# 1-voice_1_1.net
KiCad netlist of a schematic drawn in EAGLE
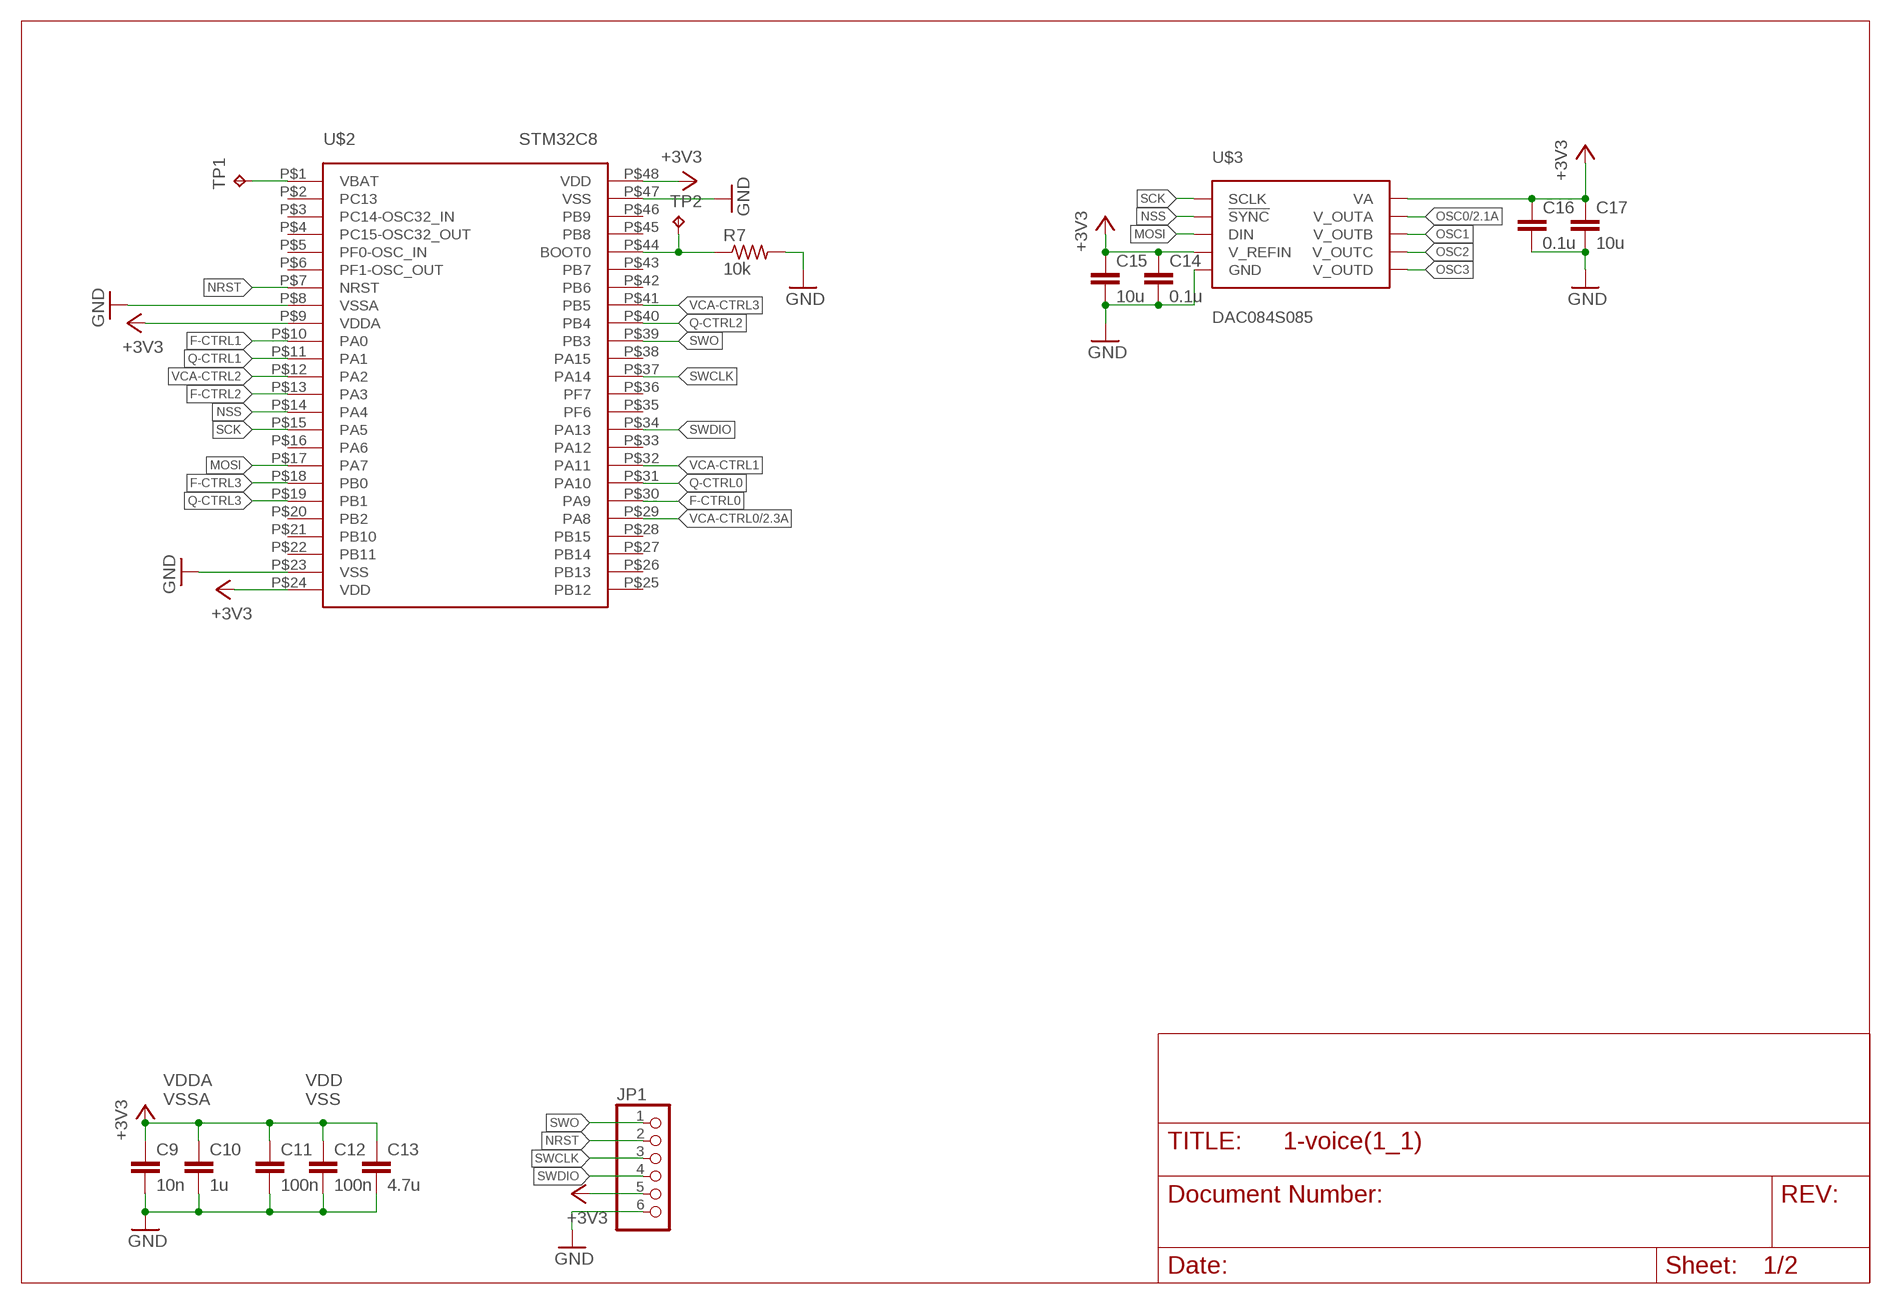
[diagram p0: schematic, sheet 1]
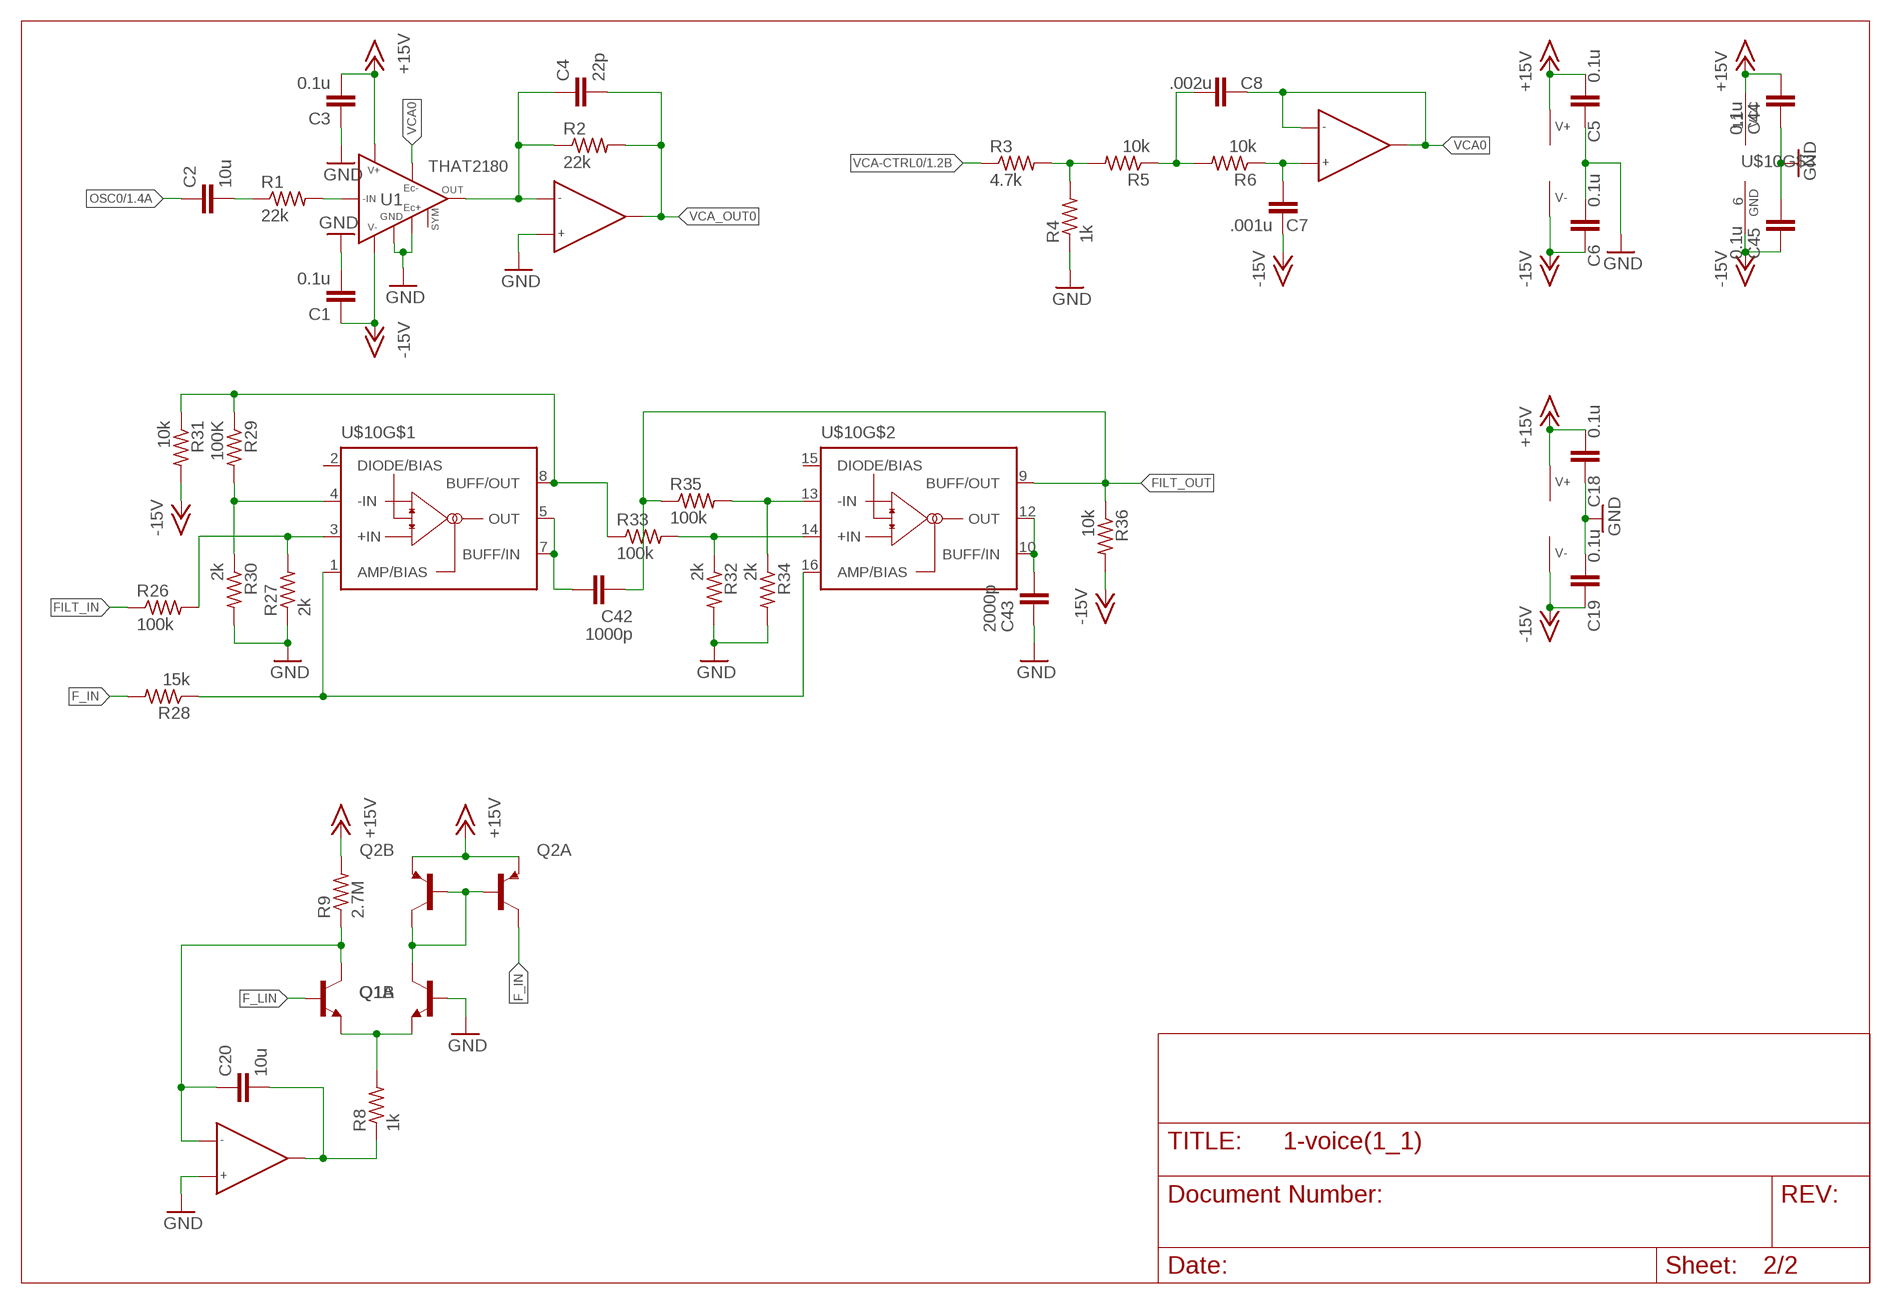
[diagram p1: schematic, sheet 2]

(export (version "E")
  (design (tool "Eeschema 10.0.6"))
  (components
    (comp (ref "C1")
      (value "0.1u")
      (footprint "eagle-import:C1206")
      (libsource (lib "eagle-import") (part "C-EUC1206"))
    )
    (comp (ref "C2")
      (value "10u")
      (footprint "eagle-import:C1206")
      (libsource (lib "eagle-import") (part "C-EUC1206"))
    )
    (comp (ref "C3")
      (value "0.1u")
      (footprint "eagle-import:C1206")
      (libsource (lib "eagle-import") (part "C-EUC1206"))
    )
    (comp (ref "C4")
      (value "22p")
      (footprint "eagle-import:C1206")
      (libsource (lib "eagle-import") (part "C-EUC1206"))
    )
    (comp (ref "C5")
      (value "0.1u")
      (footprint "eagle-import:C1206")
      (libsource (lib "eagle-import") (part "C-EUC1206"))
    )
    (comp (ref "C6")
      (value "0.1u")
      (footprint "eagle-import:C1206")
      (libsource (lib "eagle-import") (part "C-EUC1206"))
    )
    (comp (ref "C7")
      (value ".001u")
      (footprint "eagle-import:C1206")
      (libsource (lib "eagle-import") (part "C-EUC1206"))
    )
    (comp (ref "C8")
      (value ".002u")
      (footprint "eagle-import:C1206")
      (libsource (lib "eagle-import") (part "C-EUC1206"))
    )
    (comp (ref "C18")
      (value "0.1u")
      (footprint "eagle-import:C1206")
      (libsource (lib "eagle-import") (part "C-EUC1206"))
    )
    (comp (ref "C19")
      (value "0.1u")
      (footprint "eagle-import:C1206")
      (libsource (lib "eagle-import") (part "C-EUC1206"))
    )
    (comp (ref "C20")
      (value "10u")
      (footprint "eagle-import:C1206")
      (libsource (lib "eagle-import") (part "C-EUC1206"))
    )
    (comp (ref "C42")
      (value "1000p")
      (footprint "eagle-import:C1206")
      (libsource (lib "eagle-import") (part "resistor_348_C-EUC1206"))
    )
    (comp (ref "C43")
      (value "2000p")
      (footprint "eagle-import:C1206")
      (libsource (lib "eagle-import") (part "resistor_348_C-EUC1206"))
    )
    (comp (ref "C44")
      (value "0.1u")
      (footprint "eagle-import:C1206")
      (libsource (lib "eagle-import") (part "resistor_348_C-EUC1206"))
    )
    (comp (ref "C45")
      (value "0.1u")
      (footprint "eagle-import:C1206")
      (libsource (lib "eagle-import") (part "resistor_348_C-EUC1206"))
    )
    (comp (ref "Q1")
      (value "TRANS-BJT_NPN-DUAL-BC847BS-JBLMASK")
      (footprint "eagle-import:SOT-363-JBLMASK")
      (libsource (lib "eagle-import") (part "TRANS-BJT_NPN-DUAL-BC847BS-JBLMASK"))
    )
    (comp (ref "Q2")
      (value "TRANS-BJT_PNP-DUAL-BC857-JBLMASK")
      (footprint "eagle-import:SOT-363-JBLMASK")
      (libsource (lib "eagle-import") (part "TRANS-BJT_PNP-DUAL-BC857-JBLMASK"))
    )
    (comp (ref "R1")
      (value "22k")
      (footprint "eagle-import:R1206")
      (libsource (lib "eagle-import") (part "R-US_R1206"))
    )
    (comp (ref "R2")
      (value "22k")
      (footprint "eagle-import:R1206")
      (libsource (lib "eagle-import") (part "R-US_R1206"))
    )
    (comp (ref "R3")
      (value "4.7k")
      (footprint "eagle-import:R1206")
      (libsource (lib "eagle-import") (part "R-US_R1206"))
    )
    (comp (ref "R4")
      (value "1k")
      (footprint "eagle-import:R1206")
      (libsource (lib "eagle-import") (part "R-US_R1206"))
    )
    (comp (ref "R5")
      (value "10k")
      (footprint "eagle-import:R1206")
      (libsource (lib "eagle-import") (part "R-US_R1206"))
    )
    (comp (ref "R6")
      (value "10k")
      (footprint "eagle-import:R1206")
      (libsource (lib "eagle-import") (part "R-US_R1206"))
    )
    (comp (ref "R8")
      (value "1k")
      (footprint "eagle-import:R1206")
      (libsource (lib "eagle-import") (part "resistor_348_R-US_R1206"))
    )
    (comp (ref "R9")
      (value "2.7M")
      (footprint "eagle-import:R1206")
      (libsource (lib "eagle-import") (part "resistor_348_R-US_R1206"))
    )
    (comp (ref "R26")
      (value "100k")
      (footprint "eagle-import:R1206")
      (libsource (lib "eagle-import") (part "resistor_348_R-US_R1206"))
    )
    (comp (ref "R27")
      (value "2k")
      (footprint "eagle-import:R1206")
      (libsource (lib "eagle-import") (part "resistor_348_R-US_R1206"))
    )
    (comp (ref "R28")
      (value "15k")
      (footprint "eagle-import:R1206")
      (libsource (lib "eagle-import") (part "resistor_348_R-US_R1206"))
    )
    (comp (ref "R29")
      (value "100K")
      (footprint "eagle-import:R1206")
      (libsource (lib "eagle-import") (part "resistor_348_R-US_R1206"))
    )
    (comp (ref "R30")
      (value "2k")
      (footprint "eagle-import:R1206")
      (libsource (lib "eagle-import") (part "resistor_348_R-US_R1206"))
    )
    (comp (ref "R31")
      (value "10k")
      (footprint "eagle-import:R1206")
      (libsource (lib "eagle-import") (part "resistor_348_R-US_R1206"))
    )
    (comp (ref "R32")
      (value "2k")
      (footprint "eagle-import:R1206")
      (libsource (lib "eagle-import") (part "resistor_348_R-US_R1206"))
    )
    (comp (ref "R33")
      (value "100k")
      (footprint "eagle-import:R1206")
      (libsource (lib "eagle-import") (part "resistor_348_R-US_R1206"))
    )
    (comp (ref "R34")
      (value "2k")
      (footprint "eagle-import:R1206")
      (libsource (lib "eagle-import") (part "resistor_348_R-US_R1206"))
    )
    (comp (ref "R35")
      (value "100k")
      (footprint "eagle-import:R1206")
      (libsource (lib "eagle-import") (part "resistor_348_R-US_R1206"))
    )
    (comp (ref "R36")
      (value "10k")
      (footprint "eagle-import:R1206")
      (libsource (lib "eagle-import") (part "resistor_348_R-US_R1206"))
    )
    (comp (ref "U$1")
      (value "TL072")
      (footprint "eagle-import:SOIC8")
      (libsource (lib "eagle-import") (part "TL072"))
    )
    (comp (ref "U$10")
      (value "XX-13700DMP16")
      (footprint "eagle-import:DMP16")
      (libsource (lib "eagle-import") (part "XX-13700DMP16"))
    )
    (comp (ref "U$11")
      (value "TL072")
      (footprint "eagle-import:SOIC8")
      (libsource (lib "eagle-import") (part "TL072"))
    )
    (comp (ref "U1")
      (value "THAT2180")
      (footprint "eagle-import:SIP8")
      (libsource (lib "eagle-import") (part "THAT2180"))
    )
    (comp (ref "C9")
      (value "10n")
      (footprint "eagle-import:C1206")
      (libsource (lib "eagle-import") (part "C-EUC1206"))
    )
    (comp (ref "C10")
      (value "1u")
      (footprint "eagle-import:C1206")
      (libsource (lib "eagle-import") (part "C-EUC1206"))
    )
    (comp (ref "C11")
      (value "100n")
      (footprint "eagle-import:C1206")
      (libsource (lib "eagle-import") (part "C-EUC1206"))
    )
    (comp (ref "C12")
      (value "100n")
      (footprint "eagle-import:C1206")
      (libsource (lib "eagle-import") (part "C-EUC1206"))
    )
    (comp (ref "C13")
      (value "4.7u")
      (footprint "eagle-import:C1206")
      (libsource (lib "eagle-import") (part "C-EUC1206"))
    )
    (comp (ref "C14")
      (value "0.1u")
      (footprint "eagle-import:C1206")
      (libsource (lib "eagle-import") (part "C-EUC1206"))
    )
    (comp (ref "C15")
      (value "10u")
      (footprint "eagle-import:C1206")
      (libsource (lib "eagle-import") (part "C-EUC1206"))
    )
    (comp (ref "C16")
      (value "0.1u")
      (footprint "eagle-import:C1206")
      (libsource (lib "eagle-import") (part "C-EUC1206"))
    )
    (comp (ref "C17")
      (value "10u")
      (footprint "eagle-import:C1206")
      (libsource (lib "eagle-import") (part "C-EUC1206"))
    )
    (comp (ref "JP1")
      (value "PINHD-1X6")
      (footprint "eagle-import:1X06")
      (libsource (lib "eagle-import") (part "PINHD-1X6"))
    )
    (comp (ref "R7")
      (value "10k")
      (footprint "eagle-import:R1206")
      (libsource (lib "eagle-import") (part "R-US_R1206"))
    )
    (comp (ref "TP1")
      (value "TPPAD1-13")
      (footprint "eagle-import:P1-13")
      (libsource (lib "eagle-import") (part "TPPAD1-13"))
    )
    (comp (ref "TP2")
      (value "TPPAD1-13")
      (footprint "eagle-import:P1-13")
      (libsource (lib "eagle-import") (part "TPPAD1-13"))
    )
    (comp (ref "U$2")
      (value "STM32C8")
      (footprint "eagle-import:LQFP48")
      (libsource (lib "eagle-import") (part "STM32C8"))
    )
    (comp (ref "U$3")
      (value "DAC084S085")
      (footprint "eagle-import:VSSOP10")
      (libsource (lib "eagle-import") (part "DAC084S085"))
    )
  )
  (nets
    (net (code "1") (name "+3V3") (class "Default")
      (node (ref "C10") (pin "1") (pinfunction "1_1") (pintype "passive"))
      (node (ref "C11") (pin "1") (pinfunction "1_1") (pintype "passive"))
      (node (ref "C12") (pin "1") (pinfunction "1_1") (pintype "passive"))
      (node (ref "C13") (pin "1") (pinfunction "1_1") (pintype "passive"))
      (node (ref "C14") (pin "1") (pinfunction "1_1") (pintype "passive"))
      (node (ref "C15") (pin "1") (pinfunction "1_1") (pintype "passive"))
      (node (ref "C16") (pin "1") (pinfunction "1_1") (pintype "passive"))
      (node (ref "C17") (pin "1") (pinfunction "1_1") (pintype "passive"))
      (node (ref "C9") (pin "1") (pinfunction "1_1") (pintype "passive"))
      (node (ref "JP1") (pin "5") (pinfunction "5_5") (pintype "passive"))
      (node (ref "U$2") (pin "P$24") (pinfunction "VDD_P$24") (pintype "bidirectional"))
      (node (ref "U$2") (pin "P$48") (pinfunction "VDD_P$48") (pintype "bidirectional"))
      (node (ref "U$2") (pin "P$9") (pinfunction "VDDA_P$9") (pintype "bidirectional"))
      (node (ref "U$3") (pin "P$1") (pinfunction "VA_P$1") (pintype "bidirectional"))
      (node (ref "U$3") (pin "P$7") (pinfunction "V_REFIN_P$7") (pintype "bidirectional"))
    )
    (net (code "2") (name "+15V") (class "Default")
      (node (ref "C18") (pin "2") (pinfunction "2_2") (pintype "passive"))
      (node (ref "C3") (pin "2") (pinfunction "2_2") (pintype "passive"))
      (node (ref "C44") (pin "1") (pinfunction "1_1") (pintype "passive"))
      (node (ref "C5") (pin "2") (pinfunction "2_2") (pintype "passive"))
      (node (ref "Q2") (pin "1") (pinfunction "E_1") (pintype "passive"))
      (node (ref "Q2") (pin "4") (pinfunction "E_4") (pintype "passive"))
      (node (ref "R9") (pin "2") (pinfunction "2_2") (pintype "passive"))
      (node (ref "U$1") (pin "P$8") (pinfunction "V+_P$8") (pintype "bidirectional"))
      (node (ref "U$10") (pin "11") (pinfunction "VCC_11") (pintype "power_in"))
      (node (ref "U$11") (pin "P$8") (pinfunction "V+_P$8") (pintype "bidirectional"))
      (node (ref "U1") (pin "$P7") (pinfunction "V+_$P7") (pintype "bidirectional"))
    )
    (net (code "3") (name "-15V") (class "Default")
      (node (ref "C1") (pin "1") (pinfunction "1_1") (pintype "passive"))
      (node (ref "C19") (pin "1") (pinfunction "1_1") (pintype "passive"))
      (node (ref "C45") (pin "2") (pinfunction "2_2") (pintype "passive"))
      (node (ref "C6") (pin "1") (pinfunction "1_1") (pintype "passive"))
      (node (ref "C7") (pin "1") (pinfunction "1_1") (pintype "passive"))
      (node (ref "R31") (pin "2") (pinfunction "2_2") (pintype "passive"))
      (node (ref "R36") (pin "2") (pinfunction "2_2") (pintype "passive"))
      (node (ref "U$1") (pin "P$4") (pinfunction "V-_P$4") (pintype "bidirectional"))
      (node (ref "U$10") (pin "6") (pinfunction "GND_6") (pintype "power_in"))
      (node (ref "U$11") (pin "P$4") (pinfunction "V-_P$4") (pintype "bidirectional"))
      (node (ref "U1") (pin "$P5") (pinfunction "V-_$P5") (pintype "bidirectional"))
    )
    (net (code "4") (name "F-CTRL0") (class "Default")
      (node (ref "U$2") (pin "P$30") (pinfunction "PA9_P$30") (pintype "bidirectional"))
    )
    (net (code "5") (name "F-CTRL1") (class "Default")
      (node (ref "U$2") (pin "P$10") (pinfunction "PA0_P$10") (pintype "bidirectional"))
    )
    (net (code "6") (name "F-CTRL2") (class "Default")
      (node (ref "U$2") (pin "P$13") (pinfunction "PA3_P$13") (pintype "bidirectional"))
    )
    (net (code "7") (name "F-CTRL3") (class "Default")
      (node (ref "U$2") (pin "P$18") (pinfunction "PB0_P$18") (pintype "bidirectional"))
    )
    (net (code "8") (name "FILT_IN") (class "Default")
      (node (ref "R26") (pin "1") (pinfunction "1_1") (pintype "passive"))
    )
    (net (code "9") (name "FILT_OUT") (class "Default")
      (node (ref "C42") (pin "2") (pinfunction "2_2") (pintype "passive"))
      (node (ref "R35") (pin "1") (pinfunction "1_1") (pintype "passive"))
      (node (ref "R36") (pin "1") (pinfunction "1_1") (pintype "passive"))
      (node (ref "U$10") (pin "9") (pinfunction "BUFF/OUT_9") (pintype "output"))
    )
    (net (code "10") (name "F_IN") (class "Default")
      (node (ref "Q2") (pin "6") (pinfunction "C_6") (pintype "passive"))
      (node (ref "R28") (pin "2") (pinfunction "2_2") (pintype "passive"))
    )
    (net (code "11") (name "F_LIN") (class "Default")
      (node (ref "Q1") (pin "2") (pinfunction "B_2") (pintype "passive"))
    )
    (net (code "12") (name "GND") (class "Default")
      (node (ref "C1") (pin "2") (pinfunction "2_2") (pintype "passive"))
      (node (ref "C10") (pin "2") (pinfunction "2_2") (pintype "passive"))
      (node (ref "C11") (pin "2") (pinfunction "2_2") (pintype "passive"))
      (node (ref "C12") (pin "2") (pinfunction "2_2") (pintype "passive"))
      (node (ref "C13") (pin "2") (pinfunction "2_2") (pintype "passive"))
      (node (ref "C14") (pin "2") (pinfunction "2_2") (pintype "passive"))
      (node (ref "C15") (pin "2") (pinfunction "2_2") (pintype "passive"))
      (node (ref "C16") (pin "2") (pinfunction "2_2") (pintype "passive"))
      (node (ref "C17") (pin "2") (pinfunction "2_2") (pintype "passive"))
      (node (ref "C18") (pin "1") (pinfunction "1_1") (pintype "passive"))
      (node (ref "C19") (pin "2") (pinfunction "2_2") (pintype "passive"))
      (node (ref "C3") (pin "1") (pinfunction "1_1") (pintype "passive"))
      (node (ref "C43") (pin "2") (pinfunction "2_2") (pintype "passive"))
      (node (ref "C44") (pin "2") (pinfunction "2_2") (pintype "passive"))
      (node (ref "C45") (pin "1") (pinfunction "1_1") (pintype "passive"))
      (node (ref "C5") (pin "1") (pinfunction "1_1") (pintype "passive"))
      (node (ref "C6") (pin "2") (pinfunction "2_2") (pintype "passive"))
      (node (ref "C9") (pin "2") (pinfunction "2_2") (pintype "passive"))
      (node (ref "JP1") (pin "6") (pinfunction "6_6") (pintype "passive"))
      (node (ref "Q1") (pin "5") (pinfunction "B_5") (pintype "passive"))
      (node (ref "R27") (pin "1") (pinfunction "1_1") (pintype "passive"))
      (node (ref "R30") (pin "2") (pinfunction "2_2") (pintype "passive"))
      (node (ref "R32") (pin "2") (pinfunction "2_2") (pintype "passive"))
      (node (ref "R34") (pin "2") (pinfunction "2_2") (pintype "passive"))
      (node (ref "R4") (pin "1") (pinfunction "1_1") (pintype "passive"))
      (node (ref "R7") (pin "2") (pinfunction "2_2") (pintype "passive"))
      (node (ref "U$1") (pin "P$3") (pinfunction "IN+_P$3") (pintype "bidirectional"))
      (node (ref "U$11") (pin "P$3") (pinfunction "IN+_P$3") (pintype "bidirectional"))
      (node (ref "U$2") (pin "P$23") (pinfunction "VSS_P$23") (pintype "bidirectional"))
      (node (ref "U$2") (pin "P$47") (pinfunction "VSS_P$47") (pintype "bidirectional"))
      (node (ref "U$2") (pin "P$8") (pinfunction "VSSA_P$8") (pintype "bidirectional"))
      (node (ref "U$3") (pin "P$6") (pinfunction "GND_P$6") (pintype "bidirectional"))
      (node (ref "U1") (pin "$P2") (pinfunction "EC+_$P2") (pintype "bidirectional"))
      (node (ref "U1") (pin "$P6") (pinfunction "GND_$P6") (pintype "bidirectional"))
    )
    (net (code "13") (name "MOSI") (class "Default")
      (node (ref "U$2") (pin "P$17") (pinfunction "PA7_P$17") (pintype "bidirectional"))
      (node (ref "U$3") (pin "P$8") (pinfunction "DIN_P$8") (pintype "bidirectional"))
    )
    (net (code "14") (name "NRST") (class "Default")
      (node (ref "JP1") (pin "2") (pinfunction "2_2") (pintype "passive"))
      (node (ref "U$2") (pin "P$7") (pinfunction "NRST_P$7") (pintype "bidirectional"))
    )
    (net (code "15") (name "NSS") (class "Default")
      (node (ref "U$2") (pin "P$14") (pinfunction "PA4_P$14") (pintype "bidirectional"))
      (node (ref "U$3") (pin "P$9") (pinfunction "~{SYNC}_P$9") (pintype "bidirectional"))
    )
    (net (code "16") (name "Net-(C2-Pad2)") (class "Default")
      (node (ref "C2") (pin "2") (pinfunction "2_2") (pintype "passive"))
      (node (ref "R1") (pin "1") (pinfunction "1_1") (pintype "passive"))
    )
    (net (code "17") (name "Net-(C8-Pad2)") (class "Default")
      (node (ref "C8") (pin "2") (pinfunction "2_2") (pintype "passive"))
      (node (ref "R5") (pin "1") (pinfunction "1_1") (pintype "passive"))
      (node (ref "R6") (pin "2") (pinfunction "2_2") (pintype "passive"))
    )
    (net (code "18") (name "Net-(Q1A-C)") (class "Default")
      (node (ref "C20") (pin "1") (pinfunction "1_1") (pintype "passive"))
      (node (ref "Q1") (pin "6") (pinfunction "C_6") (pintype "passive"))
      (node (ref "R9") (pin "1") (pinfunction "1_1") (pintype "passive"))
      (node (ref "U$11") (pin "P$2") (pinfunction "IN-_P$2") (pintype "bidirectional"))
    )
    (net (code "19") (name "Net-(Q1A-E)") (class "Default")
      (node (ref "Q1") (pin "1") (pinfunction "E_1") (pintype "passive"))
      (node (ref "Q1") (pin "4") (pinfunction "E_4") (pintype "passive"))
      (node (ref "R8") (pin "2") (pinfunction "2_2") (pintype "passive"))
    )
    (net (code "20") (name "Net-(Q1B-C)") (class "Default")
      (node (ref "Q1") (pin "3") (pinfunction "C_3") (pintype "passive"))
      (node (ref "Q2") (pin "2") (pinfunction "B_2") (pintype "passive"))
      (node (ref "Q2") (pin "3") (pinfunction "C_3") (pintype "passive"))
      (node (ref "Q2") (pin "5") (pinfunction "B_5") (pintype "passive"))
    )
    (net (code "21") (name "Net-(R3-Pad2)") (class "Default")
      (node (ref "R3") (pin "2") (pinfunction "2_2") (pintype "passive"))
      (node (ref "R4") (pin "2") (pinfunction "2_2") (pintype "passive"))
      (node (ref "R5") (pin "2") (pinfunction "2_2") (pintype "passive"))
    )
    (net (code "22") (name "Net-(U$1A-IN-)") (class "Default")
      (node (ref "C4") (pin "1") (pinfunction "1_1") (pintype "passive"))
      (node (ref "R2") (pin "1") (pinfunction "1_1") (pintype "passive"))
      (node (ref "U$1") (pin "P$2") (pinfunction "IN-_P$2") (pintype "bidirectional"))
      (node (ref "U1") (pin "$P8") (pinfunction "OUT_$P8") (pintype "bidirectional"))
    )
    (net (code "23") (name "Net-(U$1B-IN+)") (class "Default")
      (node (ref "C7") (pin "2") (pinfunction "2_2") (pintype "passive"))
      (node (ref "R6") (pin "1") (pinfunction "1_1") (pintype "passive"))
      (node (ref "U$1") (pin "P$5") (pinfunction "IN+_P$5") (pintype "bidirectional"))
    )
    (net (code "24") (name "Net-(U$2-BOOT0)") (class "Default")
      (node (ref "R7") (pin "1") (pinfunction "1_1") (pintype "passive"))
      (node (ref "TP2") (pin "TP") (pinfunction "TP_TP") (pintype "input"))
      (node (ref "U$2") (pin "P$44") (pinfunction "BOOT0_P$44") (pintype "bidirectional"))
    )
    (net (code "25") (name "Net-(U$2-VBAT)") (class "Default")
      (node (ref "TP1") (pin "TP") (pinfunction "TP_TP") (pintype "input"))
      (node (ref "U$2") (pin "P$1") (pinfunction "VBAT_P$1") (pintype "bidirectional"))
    )
    (net (code "26") (name "Net-(U$10A-+IN)") (class "Default")
      (node (ref "R26") (pin "2") (pinfunction "2_2") (pintype "passive"))
      (node (ref "R27") (pin "2") (pinfunction "2_2") (pintype "passive"))
      (node (ref "U$10") (pin "3") (pinfunction "+IN_3") (pintype "input"))
    )
    (net (code "27") (name "Net-(U$10A--IN)") (class "Default")
      (node (ref "R29") (pin "2") (pinfunction "2_2") (pintype "passive"))
      (node (ref "R30") (pin "1") (pinfunction "1_1") (pintype "passive"))
      (node (ref "U$10") (pin "4") (pinfunction "-IN_4") (pintype "input"))
    )
    (net (code "28") (name "Net-(U$10A-AMP{slash}BIAS)") (class "Default")
      (node (ref "R28") (pin "1") (pinfunction "1_1") (pintype "passive"))
      (node (ref "U$10") (pin "1") (pinfunction "AMP/BIAS_1") (pintype "passive"))
      (node (ref "U$10") (pin "16") (pinfunction "AMP/BIAS_16") (pintype "passive"))
    )
    (net (code "29") (name "Net-(U$10A-BUFF{slash}IN)") (class "Default")
      (node (ref "C42") (pin "1") (pinfunction "1_1") (pintype "passive"))
      (node (ref "U$10") (pin "5") (pinfunction "OUT_5") (pintype "output"))
      (node (ref "U$10") (pin "7") (pinfunction "BUFF/IN_7") (pintype "input"))
    )
    (net (code "30") (name "Net-(U$10A-BUFF{slash}OUT)") (class "Default")
      (node (ref "R29") (pin "1") (pinfunction "1_1") (pintype "passive"))
      (node (ref "R31") (pin "1") (pinfunction "1_1") (pintype "passive"))
      (node (ref "R33") (pin "1") (pinfunction "1_1") (pintype "passive"))
      (node (ref "U$10") (pin "8") (pinfunction "BUFF/OUT_8") (pintype "output"))
    )
    (net (code "31") (name "Net-(U$10B-+IN)") (class "Default")
      (node (ref "R32") (pin "1") (pinfunction "1_1") (pintype "passive"))
      (node (ref "R33") (pin "2") (pinfunction "2_2") (pintype "passive"))
      (node (ref "U$10") (pin "14") (pinfunction "+IN_14") (pintype "input"))
    )
    (net (code "32") (name "Net-(U$10B--IN)") (class "Default")
      (node (ref "R34") (pin "1") (pinfunction "1_1") (pintype "passive"))
      (node (ref "R35") (pin "2") (pinfunction "2_2") (pintype "passive"))
      (node (ref "U$10") (pin "13") (pinfunction "-IN_13") (pintype "input"))
    )
    (net (code "33") (name "Net-(U$10B-BUFF{slash}IN)") (class "Default")
      (node (ref "C43") (pin "1") (pinfunction "1_1") (pintype "passive"))
      (node (ref "U$10") (pin "10") (pinfunction "BUFF/IN_10") (pintype "input"))
      (node (ref "U$10") (pin "12") (pinfunction "OUT_12") (pintype "output"))
    )
    (net (code "34") (name "Net-(U$11A-OUT)") (class "Default")
      (node (ref "C20") (pin "2") (pinfunction "2_2") (pintype "passive"))
      (node (ref "R8") (pin "1") (pinfunction "1_1") (pintype "passive"))
      (node (ref "U$11") (pin "P$1") (pinfunction "OUT_P$1") (pintype "bidirectional"))
    )
    (net (code "35") (name "Net-(U1--IN)") (class "Default")
      (node (ref "R1") (pin "2") (pinfunction "2_2") (pintype "passive"))
      (node (ref "U1") (pin "$P1") (pinfunction "-IN_$P1") (pintype "bidirectional"))
    )
    (net (code "36") (name "OSC0") (class "Default")
      (node (ref "C2") (pin "1") (pinfunction "1_1") (pintype "passive"))
      (node (ref "U$3") (pin "P$2") (pinfunction "V_OUTA_P$2") (pintype "bidirectional"))
    )
    (net (code "37") (name "OSC1") (class "Default")
      (node (ref "U$3") (pin "P$3") (pinfunction "V_OUTB_P$3") (pintype "bidirectional"))
    )
    (net (code "38") (name "OSC2") (class "Default")
      (node (ref "U$3") (pin "P$4") (pinfunction "V_OUTC_P$4") (pintype "bidirectional"))
    )
    (net (code "39") (name "OSC3") (class "Default")
      (node (ref "U$3") (pin "P$5") (pinfunction "V_OUTD_P$5") (pintype "bidirectional"))
    )
    (net (code "40") (name "Q-CTRL0") (class "Default")
      (node (ref "U$2") (pin "P$31") (pinfunction "PA10_P$31") (pintype "bidirectional"))
    )
    (net (code "41") (name "Q-CTRL1") (class "Default")
      (node (ref "U$2") (pin "P$11") (pinfunction "PA1_P$11") (pintype "bidirectional"))
    )
    (net (code "42") (name "Q-CTRL2") (class "Default")
      (node (ref "U$2") (pin "P$40") (pinfunction "PB4_P$40") (pintype "bidirectional"))
    )
    (net (code "43") (name "Q-CTRL3") (class "Default")
      (node (ref "U$2") (pin "P$19") (pinfunction "PB1_P$19") (pintype "bidirectional"))
    )
    (net (code "44") (name "SCK") (class "Default")
      (node (ref "U$2") (pin "P$15") (pinfunction "PA5_P$15") (pintype "bidirectional"))
      (node (ref "U$3") (pin "P$10") (pinfunction "SCLK_P$10") (pintype "bidirectional"))
    )
    (net (code "45") (name "SWCLK") (class "Default")
      (node (ref "JP1") (pin "3") (pinfunction "3_3") (pintype "passive"))
      (node (ref "U$2") (pin "P$37") (pinfunction "PA14_P$37") (pintype "bidirectional"))
    )
    (net (code "46") (name "SWDIO") (class "Default")
      (node (ref "JP1") (pin "4") (pinfunction "4_4") (pintype "passive"))
      (node (ref "U$2") (pin "P$34") (pinfunction "PA13_P$34") (pintype "bidirectional"))
    )
    (net (code "47") (name "SWO") (class "Default")
      (node (ref "JP1") (pin "1") (pinfunction "1_1") (pintype "passive"))
      (node (ref "U$2") (pin "P$39") (pinfunction "PB3_P$39") (pintype "bidirectional"))
    )
    (net (code "48") (name "VCA-CTRL0") (class "Default")
      (node (ref "R3") (pin "1") (pinfunction "1_1") (pintype "passive"))
      (node (ref "U$2") (pin "P$29") (pinfunction "PA8_P$29") (pintype "bidirectional"))
    )
    (net (code "49") (name "VCA-CTRL1") (class "Default")
      (node (ref "U$2") (pin "P$32") (pinfunction "PA11_P$32") (pintype "bidirectional"))
    )
    (net (code "50") (name "VCA-CTRL2") (class "Default")
      (node (ref "U$2") (pin "P$12") (pinfunction "PA2_P$12") (pintype "bidirectional"))
    )
    (net (code "51") (name "VCA-CTRL3") (class "Default")
      (node (ref "U$2") (pin "P$41") (pinfunction "PB5_P$41") (pintype "bidirectional"))
    )
    (net (code "52") (name "VCA0") (class "Default")
      (node (ref "C8") (pin "1") (pinfunction "1_1") (pintype "passive"))
      (node (ref "U$1") (pin "P$6") (pinfunction "IN-_P$6") (pintype "bidirectional"))
      (node (ref "U$1") (pin "P$7") (pinfunction "OUT_P$7") (pintype "bidirectional"))
      (node (ref "U1") (pin "$P3") (pinfunction "EC-_$P3") (pintype "bidirectional"))
    )
    (net (code "53") (name "VCA_OUT0") (class "Default")
      (node (ref "C4") (pin "2") (pinfunction "2_2") (pintype "passive"))
      (node (ref "R2") (pin "2") (pinfunction "2_2") (pintype "passive"))
      (node (ref "U$1") (pin "P$1") (pinfunction "OUT_P$1") (pintype "bidirectional"))
    )
    (net (code "54") (name "unconnected-(U$2-PA6-PadP$16)") (class "Default")
      (node (ref "U$2") (pin "P$16") (pinfunction "PA6_P$16") (pintype "bidirectional"))
    )
    (net (code "55") (name "unconnected-(U$2-PA12-PadP$33)") (class "Default")
      (node (ref "U$2") (pin "P$33") (pinfunction "PA12_P$33") (pintype "bidirectional"))
    )
    (net (code "56") (name "unconnected-(U$2-PA15-PadP$38)") (class "Default")
      (node (ref "U$2") (pin "P$38") (pinfunction "PA15_P$38") (pintype "bidirectional"))
    )
    (net (code "57") (name "unconnected-(U$2-PB2-PadP$20)") (class "Default")
      (node (ref "U$2") (pin "P$20") (pinfunction "PB2_P$20") (pintype "bidirectional"))
    )
    (net (code "58") (name "unconnected-(U$2-PB6-PadP$42)") (class "Default")
      (node (ref "U$2") (pin "P$42") (pinfunction "PB6_P$42") (pintype "bidirectional"))
    )
    (net (code "59") (name "unconnected-(U$2-PB7-PadP$43)") (class "Default")
      (node (ref "U$2") (pin "P$43") (pinfunction "PB7_P$43") (pintype "bidirectional"))
    )
    (net (code "60") (name "unconnected-(U$2-PB8-PadP$45)") (class "Default")
      (node (ref "U$2") (pin "P$45") (pinfunction "PB8_P$45") (pintype "bidirectional"))
    )
    (net (code "61") (name "unconnected-(U$2-PB9-PadP$46)") (class "Default")
      (node (ref "U$2") (pin "P$46") (pinfunction "PB9_P$46") (pintype "bidirectional"))
    )
    (net (code "62") (name "unconnected-(U$2-PB10-PadP$21)") (class "Default")
      (node (ref "U$2") (pin "P$21") (pinfunction "PB10_P$21") (pintype "bidirectional"))
    )
    (net (code "63") (name "unconnected-(U$2-PB11-PadP$22)") (class "Default")
      (node (ref "U$2") (pin "P$22") (pinfunction "PB11_P$22") (pintype "bidirectional"))
    )
    (net (code "64") (name "unconnected-(U$2-PB12-PadP$25)") (class "Default")
      (node (ref "U$2") (pin "P$25") (pinfunction "PB12_P$25") (pintype "bidirectional"))
    )
    (net (code "65") (name "unconnected-(U$2-PB13-PadP$26)") (class "Default")
      (node (ref "U$2") (pin "P$26") (pinfunction "PB13_P$26") (pintype "bidirectional"))
    )
    (net (code "66") (name "unconnected-(U$2-PB14-PadP$27)") (class "Default")
      (node (ref "U$2") (pin "P$27") (pinfunction "PB14_P$27") (pintype "bidirectional"))
    )
    (net (code "67") (name "unconnected-(U$2-PB15-PadP$28)") (class "Default")
      (node (ref "U$2") (pin "P$28") (pinfunction "PB15_P$28") (pintype "bidirectional"))
    )
    (net (code "68") (name "unconnected-(U$2-PC13-PadP$2)") (class "Default")
      (node (ref "U$2") (pin "P$2") (pinfunction "PC13_P$2") (pintype "bidirectional"))
    )
    (net (code "69") (name "unconnected-(U$2-PC14-OSC32_IN-PadP$3)") (class "Default")
      (node (ref "U$2") (pin "P$3") (pinfunction "PC14-OSC32_IN_P$3") (pintype "bidirectional"))
    )
    (net (code "70") (name "unconnected-(U$2-PC15-OSC32_OUT-PadP$4)") (class "Default")
      (node (ref "U$2") (pin "P$4") (pinfunction "PC15-OSC32_OUT_P$4") (pintype "bidirectional"))
    )
    (net (code "71") (name "unconnected-(U$2-PF0-OSC_IN-PadP$5)") (class "Default")
      (node (ref "U$2") (pin "P$5") (pinfunction "PF0-OSC_IN_P$5") (pintype "bidirectional"))
    )
    (net (code "72") (name "unconnected-(U$2-PF1-OSC_OUT-PadP$6)") (class "Default")
      (node (ref "U$2") (pin "P$6") (pinfunction "PF1-OSC_OUT_P$6") (pintype "bidirectional"))
    )
    (net (code "73") (name "unconnected-(U$2-PF6-PadP$35)") (class "Default")
      (node (ref "U$2") (pin "P$35") (pinfunction "PF6_P$35") (pintype "bidirectional"))
    )
    (net (code "74") (name "unconnected-(U$2-PF7-PadP$36)") (class "Default")
      (node (ref "U$2") (pin "P$36") (pinfunction "PF7_P$36") (pintype "bidirectional"))
    )
    (net (code "75") (name "unconnected-(U$10A-DIODE{slash}BIAS-Pad2)") (class "Default")
      (node (ref "U$10") (pin "2") (pinfunction "DIODE/BIAS_2") (pintype "passive"))
    )
    (net (code "76") (name "unconnected-(U$10B-DIODE{slash}BIAS-Pad15)") (class "Default")
      (node (ref "U$10") (pin "15") (pinfunction "DIODE/BIAS_15") (pintype "passive"))
    )
    (net (code "77") (name "unconnected-(U1-SYM-Pad$P4)") (class "Default")
      (node (ref "U1") (pin "$P4") (pinfunction "SYM_$P4") (pintype "bidirectional"))
    )
  )
)
